# gps_16_yobi.net
KiCad netlist of a schematic drawn in EAGLE
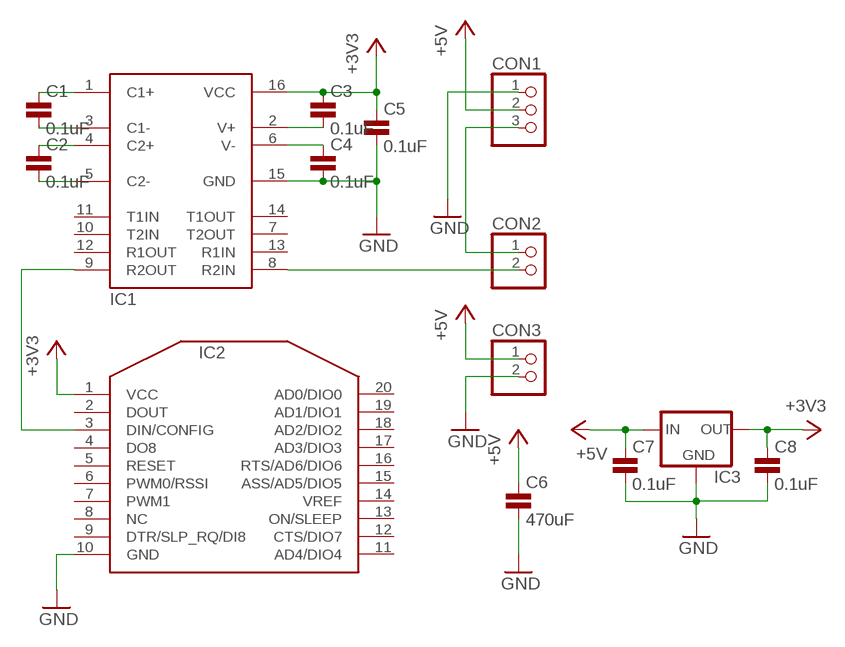
[diagram p0: schematic, sheet 1]

(export (version "E")
  (design (tool "Eeschema 10.0.6"))
  (components
    (comp (ref "C1")
      (value "0.1uF")
      (footprint "eagle-import:0603")
      (libsource (lib "eagle-import") (part "C0603"))
    )
    (comp (ref "C2")
      (value "0.1uF")
      (footprint "eagle-import:0603")
      (libsource (lib "eagle-import") (part "C0603"))
    )
    (comp (ref "C3")
      (value "0.1uF")
      (footprint "eagle-import:0603")
      (libsource (lib "eagle-import") (part "C0603"))
    )
    (comp (ref "C4")
      (value "0.1uF")
      (footprint "eagle-import:0603")
      (libsource (lib "eagle-import") (part "C0603"))
    )
    (comp (ref "C5")
      (value "0.1uF")
      (footprint "eagle-import:0603")
      (libsource (lib "eagle-import") (part "C0603"))
    )
    (comp (ref "C6")
      (value "470uF")
      (footprint "eagle-import:C025-025X050")
      (libsource (lib "eagle-import") (part "CC025-025X050"))
    )
    (comp (ref "C7")
      (value "0.1uF")
      (footprint "eagle-import:0603")
      (libsource (lib "eagle-import") (part "C0603"))
    )
    (comp (ref "C8")
      (value "0.1uF")
      (footprint "eagle-import:0603")
      (libsource (lib "eagle-import") (part "C0603"))
    )
    (comp (ref "CON1")
      (value "PINHD-1X3")
      (footprint "eagle-import:1X03")
      (libsource (lib "eagle-import") (part "PINHD-1X3"))
    )
    (comp (ref "CON2")
      (value "PINHD-1X2")
      (footprint "eagle-import:1X02")
      (libsource (lib "eagle-import") (part "PINHD-1X2"))
    )
    (comp (ref "CON3")
      (value "PINHD-1X2")
      (footprint "eagle-import:1X02")
      (libsource (lib "eagle-import") (part "PINHD-1X2"))
    )
    (comp (ref "IC1")
      (value "ADM3202ADM3202AN")
      (footprint "eagle-import:IC16PIN")
      (libsource (lib "eagle-import") (part "ADM3202ADM3202AN"))
    )
    (comp (ref "IC2")
      (value "XBEE-PRO2MM")
      (footprint "eagle-import:XBEE-ZB")
      (libsource (lib "eagle-import") (part "XBEE-PRO2MM"))
    )
    (comp (ref "IC3")
      (value "78MXXS")
      (footprint "eagle-import:78MXXS")
      (libsource (lib "eagle-import") (part "78MXXS"))
    )
  )
  (nets
    (net (code "1") (name "+3V3") (class "Default")
      (node (ref "C3") (pin "1") (pinfunction "P$1_1") (pintype "passive"))
      (node (ref "C5") (pin "1") (pinfunction "P$1_1") (pintype "passive"))
      (node (ref "C8") (pin "1") (pinfunction "P$1_1") (pintype "passive"))
      (node (ref "IC1") (pin "16") (pinfunction "VCC_16") (pintype "bidirectional"))
      (node (ref "IC2") (pin "1") (pinfunction "VCC_1") (pintype "bidirectional"))
      (node (ref "IC3") (pin "OUT") (pinfunction "OUT_OUT") (pintype "passive"))
    )
    (net (code "2") (name "+5V") (class "Default")
      (node (ref "C6") (pin "1") (pinfunction "P$1_1") (pintype "passive"))
      (node (ref "C7") (pin "1") (pinfunction "P$1_1") (pintype "passive"))
      (node (ref "CON1") (pin "2") (pinfunction "2_2") (pintype "passive"))
      (node (ref "CON3") (pin "1") (pinfunction "1_1") (pintype "passive"))
      (node (ref "IC3") (pin "IN") (pinfunction "IN_IN") (pintype "input"))
    )
    (net (code "3") (name "GND") (class "Default")
      (node (ref "C4") (pin "2") (pinfunction "P$2_2") (pintype "passive"))
      (node (ref "C5") (pin "2") (pinfunction "P$2_2") (pintype "passive"))
      (node (ref "C6") (pin "2") (pinfunction "P$2_2") (pintype "passive"))
      (node (ref "C7") (pin "2") (pinfunction "P$2_2") (pintype "passive"))
      (node (ref "C8") (pin "2") (pinfunction "P$2_2") (pintype "passive"))
      (node (ref "CON1") (pin "1") (pinfunction "1_1") (pintype "passive"))
      (node (ref "CON3") (pin "2") (pinfunction "2_2") (pintype "passive"))
      (node (ref "IC1") (pin "15") (pinfunction "GND_15") (pintype "bidirectional"))
      (node (ref "IC2") (pin "10") (pinfunction "GND_10") (pintype "bidirectional"))
      (node (ref "IC3") (pin "GND") (pinfunction "GND_GND") (pintype "input"))
    )
    (net (code "4") (name "Net-(C1-P$1)") (class "Default")
      (node (ref "C1") (pin "1") (pinfunction "P$1_1") (pintype "passive"))
      (node (ref "IC1") (pin "1") (pinfunction "C1+_1") (pintype "bidirectional"))
    )
    (net (code "5") (name "Net-(C1-P$2)") (class "Default")
      (node (ref "C1") (pin "2") (pinfunction "P$2_2") (pintype "passive"))
      (node (ref "IC1") (pin "3") (pinfunction "C1-_3") (pintype "bidirectional"))
    )
    (net (code "6") (name "Net-(C2-P$1)") (class "Default")
      (node (ref "C2") (pin "1") (pinfunction "P$1_1") (pintype "passive"))
      (node (ref "IC1") (pin "4") (pinfunction "C2+_4") (pintype "bidirectional"))
    )
    (net (code "7") (name "Net-(C2-P$2)") (class "Default")
      (node (ref "C2") (pin "2") (pinfunction "P$2_2") (pintype "passive"))
      (node (ref "IC1") (pin "5") (pinfunction "C2-_5") (pintype "bidirectional"))
    )
    (net (code "8") (name "Net-(C3-P$2)") (class "Default")
      (node (ref "C3") (pin "2") (pinfunction "P$2_2") (pintype "passive"))
      (node (ref "IC1") (pin "2") (pinfunction "V+_2") (pintype "bidirectional"))
    )
    (net (code "9") (name "Net-(C4-P$1)") (class "Default")
      (node (ref "C4") (pin "1") (pinfunction "P$1_1") (pintype "passive"))
      (node (ref "IC1") (pin "6") (pinfunction "V-_6") (pintype "bidirectional"))
    )
    (net (code "10") (name "Net-(CON1-Pad3)") (class "Default")
      (node (ref "CON1") (pin "3") (pinfunction "3_3") (pintype "passive"))
      (node (ref "CON2") (pin "1") (pinfunction "1_1") (pintype "passive"))
    )
    (net (code "11") (name "Net-(IC1-R2IN)") (class "Default")
      (node (ref "CON2") (pin "2") (pinfunction "2_2") (pintype "passive"))
      (node (ref "IC1") (pin "8") (pinfunction "R2IN_8") (pintype "bidirectional"))
    )
    (net (code "12") (name "Net-(IC1-R2OUT)") (class "Default")
      (node (ref "IC1") (pin "9") (pinfunction "R2OUT_9") (pintype "bidirectional"))
      (node (ref "IC2") (pin "3") (pinfunction "DIN/CONFIG_3") (pintype "bidirectional"))
    )
    (net (code "13") (name "unconnected-(IC1-R1IN-Pad13)") (class "Default")
      (node (ref "IC1") (pin "13") (pinfunction "R1IN_13") (pintype "bidirectional"))
    )
    (net (code "14") (name "unconnected-(IC1-R1OUT-Pad12)") (class "Default")
      (node (ref "IC1") (pin "12") (pinfunction "R1OUT_12") (pintype "bidirectional"))
    )
    (net (code "15") (name "unconnected-(IC1-T1IN-Pad11)") (class "Default")
      (node (ref "IC1") (pin "11") (pinfunction "T1IN_11") (pintype "bidirectional"))
    )
    (net (code "16") (name "unconnected-(IC1-T1OUT-Pad14)") (class "Default")
      (node (ref "IC1") (pin "14") (pinfunction "T1OUT_14") (pintype "bidirectional"))
    )
    (net (code "17") (name "unconnected-(IC1-T2IN-Pad10)") (class "Default")
      (node (ref "IC1") (pin "10") (pinfunction "T2IN_10") (pintype "bidirectional"))
    )
    (net (code "18") (name "unconnected-(IC1-T2OUT-Pad7)") (class "Default")
      (node (ref "IC1") (pin "7") (pinfunction "T2OUT_7") (pintype "bidirectional"))
    )
    (net (code "19") (name "unconnected-(IC2-AD0{slash}DIO0-Pad20)") (class "Default")
      (node (ref "IC2") (pin "20") (pinfunction "AD0/DIO0_20") (pintype "bidirectional"))
    )
    (net (code "20") (name "unconnected-(IC2-AD1{slash}DIO1-Pad19)") (class "Default")
      (node (ref "IC2") (pin "19") (pinfunction "AD1/DIO1_19") (pintype "bidirectional"))
    )
    (net (code "21") (name "unconnected-(IC2-AD2{slash}DIO2-Pad18)") (class "Default")
      (node (ref "IC2") (pin "18") (pinfunction "AD2/DIO2_18") (pintype "bidirectional"))
    )
    (net (code "22") (name "unconnected-(IC2-AD3{slash}DIO3-Pad17)") (class "Default")
      (node (ref "IC2") (pin "17") (pinfunction "AD3/DIO3_17") (pintype "bidirectional"))
    )
    (net (code "23") (name "unconnected-(IC2-AD4{slash}DIO4-Pad11)") (class "Default")
      (node (ref "IC2") (pin "11") (pinfunction "AD4/DIO4_11") (pintype "bidirectional"))
    )
    (net (code "24") (name "unconnected-(IC2-ASS{slash}AD5{slash}DIO5-Pad15)") (class "Default")
      (node (ref "IC2") (pin "15") (pinfunction "ASS/AD5/DIO5_15") (pintype "bidirectional"))
    )
    (net (code "25") (name "unconnected-(IC2-CTS{slash}DIO7-Pad12)") (class "Default")
      (node (ref "IC2") (pin "12") (pinfunction "CTS/DIO7_12") (pintype "bidirectional"))
    )
    (net (code "26") (name "unconnected-(IC2-DO8-Pad4)") (class "Default")
      (node (ref "IC2") (pin "4") (pinfunction "DO8_4") (pintype "bidirectional"))
    )
    (net (code "27") (name "unconnected-(IC2-DOUT-Pad2)") (class "Default")
      (node (ref "IC2") (pin "2") (pinfunction "DOUT_2") (pintype "bidirectional"))
    )
    (net (code "28") (name "unconnected-(IC2-DTR{slash}SLP_RQ{slash}DI8-Pad9)") (class "Default")
      (node (ref "IC2") (pin "9") (pinfunction "DTR/SLP_RQ/DI8_9") (pintype "bidirectional"))
    )
    (net (code "29") (name "unconnected-(IC2-NC-Pad8)") (class "Default")
      (node (ref "IC2") (pin "8") (pinfunction "NC_8") (pintype "bidirectional"))
    )
    (net (code "30") (name "unconnected-(IC2-ON{slash}SLEEP-Pad13)") (class "Default")
      (node (ref "IC2") (pin "13") (pinfunction "ON/SLEEP_13") (pintype "bidirectional"))
    )
    (net (code "31") (name "unconnected-(IC2-PWM0{slash}RSSI-Pad6)") (class "Default")
      (node (ref "IC2") (pin "6") (pinfunction "PWM0/RSSI_6") (pintype "bidirectional"))
    )
    (net (code "32") (name "unconnected-(IC2-PWM1-Pad7)") (class "Default")
      (node (ref "IC2") (pin "7") (pinfunction "PWM1_7") (pintype "bidirectional"))
    )
    (net (code "33") (name "unconnected-(IC2-RESET-Pad5)") (class "Default")
      (node (ref "IC2") (pin "5") (pinfunction "RESET_5") (pintype "bidirectional"))
    )
    (net (code "34") (name "unconnected-(IC2-RTS{slash}AD6{slash}DIO6-Pad16)") (class "Default")
      (node (ref "IC2") (pin "16") (pinfunction "RTS/AD6/DIO6_16") (pintype "bidirectional"))
    )
    (net (code "35") (name "unconnected-(IC2-VREF-Pad14)") (class "Default")
      (node (ref "IC2") (pin "14") (pinfunction "VREF_14") (pintype "bidirectional"))
    )
  )
)
